# Power_DDRTermination.net
KiCad netlist of a schematic drawn in Altium Designer
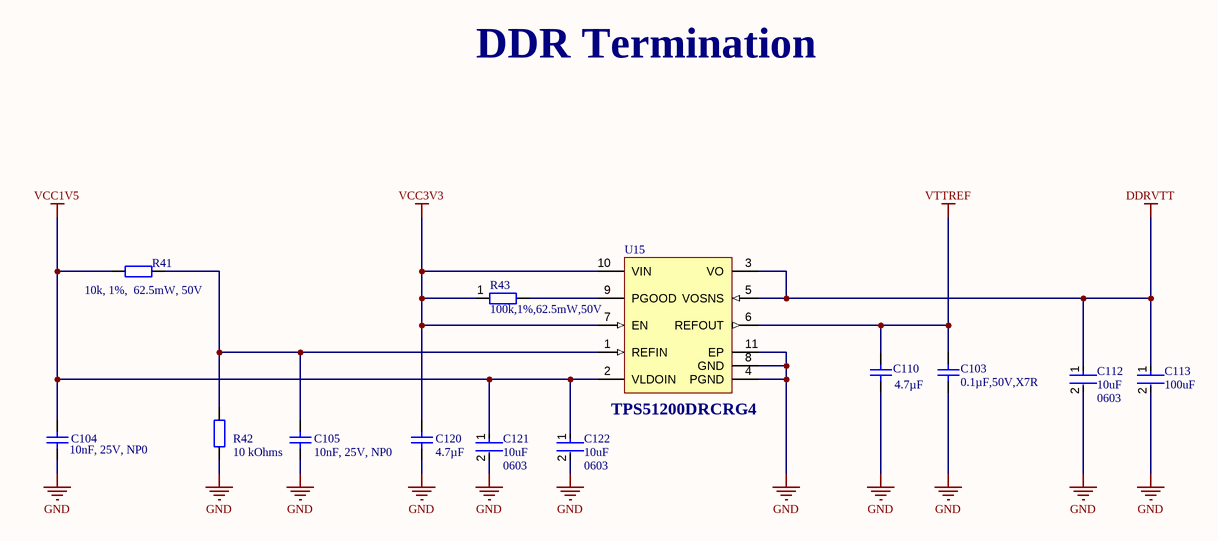
[diagram p0: Power_DDRTermination.SchDoc]

(export (version "E")
  (design (tool "Eeschema 10.0.6"))
  (components
    (comp (ref "C103")
      (value "0.1µF,50V,X7R")
      (footprint "CAP0402i")
      (description "0402, 0.1uF, 10%,  50V, X7R")
      (fields (field (name "PART NUMBER") "C1005X7R1H104K050BE") (field (name "VOLTAGE") "50V"))
      (libsource (lib "AmpherLib") (part "Cap_0.1uF_50V_X7R_0402"))
    )
    (comp (ref "C104")
      (value "10nF, 25V, NP0")
      (footprint "CAP0402i")
      (description "0402,10nF,5%,25V,NP0")
      (fields (field (name "PART NUMBER") "GRM1555C1E103JE01J") (field (name "MANUFACTURER") "Murata"))
      (libsource (lib "AmpherLib") (part "Cap_10nF_25V_NP0_0402"))
    )
    (comp (ref "C105")
      (value "10nF, 25V, NP0")
      (footprint "CAP0402i")
      (description "0402,10nF,5%,25V,NP0")
      (fields (field (name "PART NUMBER") "GRM1555C1E103JE01J") (field (name "MANUFACTURER") "Murata"))
      (libsource (lib "AmpherLib") (part "Cap_10nF_25V_NP0_0402"))
    )
    (comp (ref "C110")
      (value "4.7µF")
      (footprint "CAP0402i")
      (description "CAP CER 4.7UF 10V X5R 0402")
      (fields
        (field (name "TOLERANCE") "10%")
        (field (name "CAPACITANCE") "4.7µF")
        (field (name "PART NUMBER") "C1005X5R1A475K050BC")
      )
      (libsource (lib "AmpherLib") (part "Cap_4.7uF_10V_10%_0402"))
    )
    (comp (ref "C112")
      (value "GRM188R60J106ME47D")
      (footprint "FP-GRM188-0_1-e0_2_0_55-IPC_A")
      (description "Chip Multilayer Ceramic Capacitors for General Purpose, 0603, 10uF, X5R, 15%, 20%, 6.3V")
      (fields
        (field (name "CAPACITANCE") "10uF")
        (field (name "CASE/PACKAGE") "0603")
        (field (name "VOLTAGE") "6.3V")
        (field (name "TOLERANCE") "20%")
      )
      (libsource (lib "Altium Content Vault") (part "02cd4be3c70576c341d710602a673aa"))
    )
    (comp (ref "C113")
      (value "100uF")
      (footprint "FP-GRM32-0_3-MFG")
      (description "CAP CER 100UF 6.3V X5R 1210")
      (fields
        (field (name "OCTOPART") "https://octopart.com/grm32er60j107me20l-murata-197007")
        (field (name "3DS PART NUMBER") "220-00002")
      )
      (libsource (lib "Altium Content Vault") (part "11868f565c42a9108669ba33697ecf6"))
    )
    (comp (ref "C120")
      (value "4.7µF")
      (footprint "CAP0402i")
      (description "CAP CER 4.7UF 10V X5R 0402")
      (fields
        (field (name "TOLERANCE") "10%")
        (field (name "CAPACITANCE") "4.7µF")
        (field (name "PART NUMBER") "C1005X5R1A475K050BC")
      )
      (libsource (lib "AmpherLib") (part "Cap_4.7uF_10V_10%_0402"))
    )
    (comp (ref "C121")
      (value "GRM188R60J106ME47D")
      (footprint "FP-GRM188-0_1-e0_2_0_55-IPC_A")
      (description "Chip Multilayer Ceramic Capacitors for General Purpose, 0603, 10uF, X5R, 15%, 20%, 6.3V")
      (fields
        (field (name "CAPACITANCE") "10uF")
        (field (name "CASE/PACKAGE") "0603")
        (field (name "VOLTAGE") "6.3V")
        (field (name "TOLERANCE") "20%")
      )
      (libsource (lib "Altium Content Vault") (part "02cd4be3c70576c341d710602a673aa"))
    )
    (comp (ref "C122")
      (value "GRM188R60J106ME47D")
      (footprint "FP-GRM188-0_1-e0_2_0_55-IPC_A")
      (description "Chip Multilayer Ceramic Capacitors for General Purpose, 0603, 10uF, X5R, 15%, 20%, 6.3V")
      (fields
        (field (name "CAPACITANCE") "10uF")
        (field (name "CASE/PACKAGE") "0603")
        (field (name "VOLTAGE") "6.3V")
        (field (name "TOLERANCE") "20%")
      )
      (libsource (lib "Altium Content Vault") (part "02cd4be3c70576c341d710602a673aa"))
    )
    (comp (ref "R41")
      (value "10k, 1%,  62.5mW, 50V")
      (footprint "RES0402i")
      (description "0402, 10K 1%,  62.5mW, 50V")
      (fields (field (name "PART NUMBER") "CR0402-FX-1002GLF") (field (name "VOLTAGE") "50V"))
      (libsource (lib "AmpherLib") (part "Res_10k_1%_0402"))
    )
    (comp (ref "R42")
      (value "10 kOhms")
      (footprint "RES0402i")
      (description "0402, 10K 1%,  62.5mW, 50V")
      (fields
        (field (name "PART NUMBER") "CR0402-FX-1002GLF")
        (field (name "VOLTAGE") "50V")
        (field (name "RESISTANCE") "10 kOhms")
      )
      (libsource (lib "") (part "Res_10k_1%_0402_1"))
    )
    (comp (ref "R43")
      (value "100k,1%,62.5mW,50V")
      (footprint "RES0402i")
      (description "0402, 100k, 1%, 62.5mW, 50V")
      (fields (field (name "PART NUMBER") "CR0402-FX-1003GLF") (field (name "VOLTAGE") "50 V"))
      (libsource (lib "AmpherLib") (part "Res_100K_1%_0402"))
    )
    (comp (ref "U15")
      (value "TPS51200DRCRG4")
      (footprint "TI-DRC10-2400X1650TP_V")
      (fields (field (name "MANUFACTURER") "Texas Instruments"))
      (libsource (lib "Altium Content Vault") (part "TI-TPS51200DRC10-2400X1650TP"))
    )
  )
  (nets
    (net (code "1") (name "DDRVTT") (class "Default")
      (node (ref "C112") (pin "1") (pinfunction "1_1") (pintype "passive"))
      (node (ref "C113") (pin "1") (pinfunction "1_1") (pintype "passive"))
      (node (ref "U15") (pin "3") (pinfunction "VO_3") (pintype "power_in"))
      (node (ref "U15") (pin "5") (pinfunction "VOSNS_5") (pintype "input"))
    )
    (net (code "2") (name "GND") (class "Default")
      (node (ref "C103") (pin "1") (pinfunction "1_1") (pintype "passive"))
      (node (ref "C104") (pin "1") (pinfunction "1_1") (pintype "passive"))
      (node (ref "C105") (pin "1") (pinfunction "1_1") (pintype "passive"))
      (node (ref "C110") (pin "1") (pinfunction "1_1") (pintype "passive"))
      (node (ref "C112") (pin "2") (pinfunction "2_2") (pintype "passive"))
      (node (ref "C113") (pin "2") (pinfunction "2_2") (pintype "passive"))
      (node (ref "C120") (pin "1") (pinfunction "1_1") (pintype "passive"))
      (node (ref "C121") (pin "2") (pinfunction "2_2") (pintype "passive"))
      (node (ref "C122") (pin "2") (pinfunction "2_2") (pintype "passive"))
      (node (ref "R42") (pin "1") (pinfunction "1_1") (pintype "passive"))
      (node (ref "U15") (pin "11") (pinfunction "EP_11") (pintype "power_in"))
      (node (ref "U15") (pin "4") (pinfunction "PGND_4") (pintype "power_in"))
      (node (ref "U15") (pin "8") (pinfunction "GND_8") (pintype "power_in"))
    )
    (net (code "3") (name "Net-(U15-PGOOD)") (class "Default")
      (node (ref "R43") (pin "2") (pinfunction "2_2") (pintype "passive"))
      (node (ref "U15") (pin "9") (pinfunction "PGOOD_9") (pintype "open_collector"))
    )
    (net (code "4") (name "Net-(U15-REFIN)") (class "Default")
      (node (ref "C105") (pin "2") (pinfunction "2_2") (pintype "passive"))
      (node (ref "R41") (pin "2") (pinfunction "2_2") (pintype "passive"))
      (node (ref "R42") (pin "2") (pinfunction "2_2") (pintype "passive"))
      (node (ref "U15") (pin "1") (pinfunction "REFIN_1") (pintype "input"))
    )
    (net (code "5") (name "VCC1V5") (class "Default")
      (node (ref "C104") (pin "2") (pinfunction "2_2") (pintype "passive"))
      (node (ref "C121") (pin "1") (pinfunction "1_1") (pintype "passive"))
      (node (ref "C122") (pin "1") (pinfunction "1_1") (pintype "passive"))
      (node (ref "R41") (pin "1") (pinfunction "1_1") (pintype "passive"))
      (node (ref "U15") (pin "2") (pinfunction "VLDOIN_2") (pintype "power_in"))
    )
    (net (code "6") (name "VCC3V3") (class "Default")
      (node (ref "C120") (pin "2") (pinfunction "2_2") (pintype "passive"))
      (node (ref "R43") (pin "1") (pinfunction "1_1") (pintype "passive"))
      (node (ref "U15") (pin "10") (pinfunction "VIN_10") (pintype "power_in"))
      (node (ref "U15") (pin "7") (pinfunction "EN_7") (pintype "input"))
    )
    (net (code "7") (name "VTTREF") (class "Default")
      (node (ref "C103") (pin "2") (pinfunction "2_2") (pintype "passive"))
      (node (ref "C110") (pin "2") (pinfunction "2_2") (pintype "passive"))
      (node (ref "U15") (pin "6") (pinfunction "REFOUT_6") (pintype "output"))
    )
  )
)
